# nf10_addon.net
KiCad netlist of a schematic drawn in Altium Designer
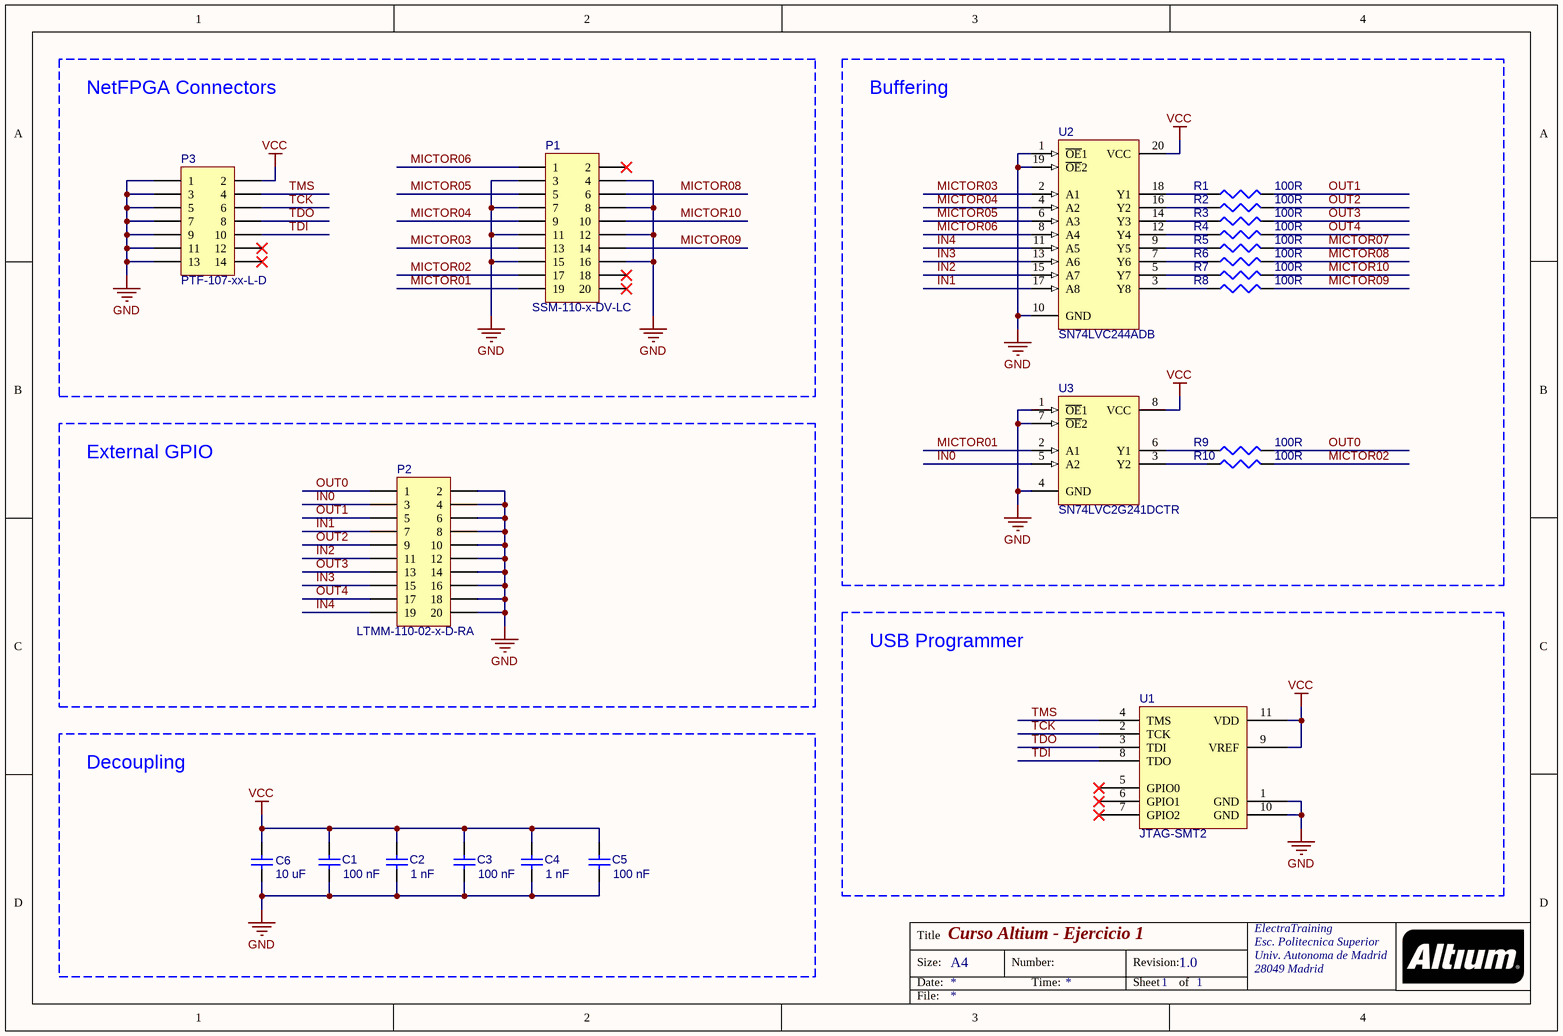
[diagram p0: nf10_addon.SchDoc]

(export (version "E")
  (design (tool "Eeschema 10.0.6"))
  (components
    (comp (ref "C1")
      (value "100 nF")
      (footprint "CAPC0603(1608)100_N")
      (description "Capacitor")
      (fields (field (name "Comment") "Cap") (field (name "PUBLISHER") "Altium Limited"))
      (libsource (lib "Miscellaneous Devices") (part "Cap"))
    )
    (comp (ref "C2")
      (value "1 nF")
      (footprint "CAPC0603(1608)100_N")
      (description "Capacitor")
      (fields (field (name "Comment") "Cap") (field (name "PUBLISHER") "Altium Limited"))
      (libsource (lib "Miscellaneous Devices") (part "Cap"))
    )
    (comp (ref "C3")
      (value "100 nF")
      (footprint "CAPC0603(1608)100_N")
      (description "Capacitor")
      (fields (field (name "Comment") "Cap") (field (name "PUBLISHER") "Altium Limited"))
      (libsource (lib "Miscellaneous Devices") (part "Cap"))
    )
    (comp (ref "C4")
      (value "1 nF")
      (footprint "CAPC0603(1608)100_N")
      (description "Capacitor")
      (fields (field (name "Comment") "Cap") (field (name "PUBLISHER") "Altium Limited"))
      (libsource (lib "Miscellaneous Devices") (part "Cap"))
    )
    (comp (ref "C5")
      (value "100 nF")
      (footprint "CAPC0603(1608)100_N")
      (description "Capacitor")
      (fields (field (name "Comment") "Cap") (field (name "PUBLISHER") "Altium Limited"))
      (libsource (lib "Miscellaneous Devices") (part "Cap"))
    )
    (comp (ref "C6")
      (value "10 uF")
      (footprint "CAPC1206(3216)100_N")
      (description "Capacitor")
      (fields (field (name "Comment") "Cap") (field (name "PUBLISHER") "Altium Limited"))
      (libsource (lib "Miscellaneous Devices") (part "Cap"))
    )
    (comp (ref "P1")
      (value "SSM-110-x-DV-LC")
      (footprint "SSM-110-X-DV-LC")
      (description "Samtec SSM-110-x-DV-LC")
      (fields (field (name "PUBLISHER") "Altium Limited"))
      (libsource (lib "nf10_addon") (part "SSM-110-x-DV-LC"))
    )
    (comp (ref "P2")
      (value "LTMM-110-02-x-D-RA")
      (footprint "LTMM-110-02-X-D-RA")
      (description "Samtec LTMM-110-02-x-D-RA")
      (fields (field (name "PUBLISHER") "Altium Limited"))
      (libsource (lib "nf10_addon") (part "LTMM-110-02-x-D-RA"))
    )
    (comp (ref "P3")
      (value "PTF-107-xx-L-D")
      (footprint "PTF-107-XX-L-D")
      (description "Samtec PTF-107-xx-L-D")
      (fields (field (name "PUBLISHER") "Altium Limited"))
      (libsource (lib "nf10_addon") (part "PTF-107-xx-L-D"))
    )
    (comp (ref "R1")
      (value "100R")
      (footprint "RESC0603(1608)_N")
      (description "Resistor")
      (fields (field (name "Comment") "Res3") (field (name "PUBLISHER") "Altium Limited"))
      (libsource (lib "Miscellaneous Devices") (part "Res3"))
    )
    (comp (ref "R2")
      (value "100R")
      (footprint "RESC0603(1608)_N")
      (description "Resistor")
      (fields (field (name "Comment") "Res3") (field (name "PUBLISHER") "Altium Limited"))
      (libsource (lib "Miscellaneous Devices") (part "Res3"))
    )
    (comp (ref "R3")
      (value "100R")
      (footprint "RESC0603(1608)_N")
      (description "Resistor")
      (fields (field (name "Comment") "Res3") (field (name "PUBLISHER") "Altium Limited"))
      (libsource (lib "Miscellaneous Devices") (part "Res3"))
    )
    (comp (ref "R4")
      (value "100R")
      (footprint "RESC0603(1608)_N")
      (description "Resistor")
      (fields (field (name "Comment") "Res3") (field (name "PUBLISHER") "Altium Limited"))
      (libsource (lib "Miscellaneous Devices") (part "Res3"))
    )
    (comp (ref "R5")
      (value "100R")
      (footprint "RESC0603(1608)_N")
      (description "Resistor")
      (fields (field (name "Comment") "Res3") (field (name "PUBLISHER") "Altium Limited"))
      (libsource (lib "Miscellaneous Devices") (part "Res3"))
    )
    (comp (ref "R6")
      (value "100R")
      (footprint "RESC0603(1608)_N")
      (description "Resistor")
      (fields (field (name "Comment") "Res3") (field (name "PUBLISHER") "Altium Limited"))
      (libsource (lib "Miscellaneous Devices") (part "Res3"))
    )
    (comp (ref "R7")
      (value "100R")
      (footprint "RESC0603(1608)_N")
      (description "Resistor")
      (fields (field (name "Comment") "Res3") (field (name "PUBLISHER") "Altium Limited"))
      (libsource (lib "Miscellaneous Devices") (part "Res3"))
    )
    (comp (ref "R8")
      (value "100R")
      (footprint "RESC0603(1608)_N")
      (description "Resistor")
      (fields (field (name "Comment") "Res3") (field (name "PUBLISHER") "Altium Limited"))
      (libsource (lib "Miscellaneous Devices") (part "Res3"))
    )
    (comp (ref "R9")
      (value "100R")
      (footprint "RESC0603(1608)_N")
      (description "Resistor")
      (fields (field (name "Comment") "Res3") (field (name "PUBLISHER") "Altium Limited"))
      (libsource (lib "Miscellaneous Devices") (part "Res3"))
    )
    (comp (ref "R10")
      (value "100R")
      (footprint "RESC0603(1608)_N")
      (description "Resistor")
      (fields (field (name "Comment") "Res3") (field (name "PUBLISHER") "Altium Limited"))
      (libsource (lib "Miscellaneous Devices") (part "Res3"))
    )
    (comp (ref "U1")
      (value "JTAG-SMT2")
      (footprint "JTAG-SMT2")
      (libsource (lib "NetFPGA10G_Addon") (part "JTAG_SMT2"))
    )
    (comp (ref "U2")
      (value "SN74LVC244ADB")
      (footprint "DB020_N")
      (description "Octal Buffer/Driver with 3-State Outputs")
      (fields (field (name "PUBLISHER") "Altium Limited"))
      (libsource (lib "TI Logic Buffer Line Driver") (part "SN74LVC244ADB"))
    )
    (comp (ref "U3")
      (value "SN74LVC2G241DCTR")
      (footprint "DCT08_N")
      (description "Quadruple Bus Buffer Gate with 3- State Outputs")
      (fields (field (name "PUBLISHER") "Altium Limited"))
      (libsource (lib "nf10_addon") (part "SN74LVC2G241DCTR"))
    )
  )
  (nets
    (net (code "1") (name "/IN0") (class "Default")
      (node (ref "P2") (pin "3") (pinfunction "3_3") (pintype "passive"))
      (node (ref "U3") (pin "5") (pinfunction "A2_5") (pintype "input"))
    )
    (net (code "2") (name "/IN1") (class "Default")
      (node (ref "P2") (pin "7") (pinfunction "7_7") (pintype "passive"))
      (node (ref "U2") (pin "17") (pinfunction "A8_17") (pintype "input"))
    )
    (net (code "3") (name "/IN2") (class "Default")
      (node (ref "P2") (pin "11") (pinfunction "11_11") (pintype "passive"))
      (node (ref "U2") (pin "15") (pinfunction "A7_15") (pintype "input"))
    )
    (net (code "4") (name "/IN3") (class "Default")
      (node (ref "P2") (pin "15") (pinfunction "15_15") (pintype "passive"))
      (node (ref "U2") (pin "13") (pinfunction "A6_13") (pintype "input"))
    )
    (net (code "5") (name "/IN4") (class "Default")
      (node (ref "P2") (pin "19") (pinfunction "19_19") (pintype "passive"))
      (node (ref "U2") (pin "11") (pinfunction "A5_11") (pintype "input"))
    )
    (net (code "6") (name "/MICTOR01") (class "Default")
      (node (ref "P1") (pin "19") (pinfunction "19_19") (pintype "passive"))
      (node (ref "U3") (pin "2") (pinfunction "A1_2") (pintype "input"))
    )
    (net (code "7") (name "/MICTOR02") (class "Default")
      (node (ref "P1") (pin "17") (pinfunction "17_17") (pintype "passive"))
      (node (ref "R10") (pin "2") (pinfunction "2_2") (pintype "passive"))
    )
    (net (code "8") (name "/MICTOR03") (class "Default")
      (node (ref "P1") (pin "13") (pinfunction "13_13") (pintype "passive"))
      (node (ref "U2") (pin "2") (pinfunction "A1_2") (pintype "input"))
    )
    (net (code "9") (name "/MICTOR04") (class "Default")
      (node (ref "P1") (pin "9") (pinfunction "9_9") (pintype "passive"))
      (node (ref "U2") (pin "4") (pinfunction "A2_4") (pintype "input"))
    )
    (net (code "10") (name "/MICTOR05") (class "Default")
      (node (ref "P1") (pin "5") (pinfunction "5_5") (pintype "passive"))
      (node (ref "U2") (pin "6") (pinfunction "A3_6") (pintype "input"))
    )
    (net (code "11") (name "/MICTOR06") (class "Default")
      (node (ref "P1") (pin "1") (pinfunction "1_1") (pintype "passive"))
      (node (ref "U2") (pin "8") (pinfunction "A4_8") (pintype "input"))
    )
    (net (code "12") (name "/MICTOR07") (class "Default")
      (node (ref "R5") (pin "2") (pinfunction "2_2") (pintype "passive"))
    )
    (net (code "13") (name "/MICTOR08") (class "Default")
      (node (ref "P1") (pin "6") (pinfunction "6_6") (pintype "passive"))
      (node (ref "R6") (pin "2") (pinfunction "2_2") (pintype "passive"))
    )
    (net (code "14") (name "/MICTOR09") (class "Default")
      (node (ref "P1") (pin "14") (pinfunction "14_14") (pintype "passive"))
      (node (ref "R8") (pin "2") (pinfunction "2_2") (pintype "passive"))
    )
    (net (code "15") (name "/MICTOR10") (class "Default")
      (node (ref "P1") (pin "10") (pinfunction "10_10") (pintype "passive"))
      (node (ref "R7") (pin "2") (pinfunction "2_2") (pintype "passive"))
    )
    (net (code "16") (name "/OUT0") (class "Default")
      (node (ref "P2") (pin "1") (pinfunction "1_1") (pintype "passive"))
      (node (ref "R9") (pin "2") (pinfunction "2_2") (pintype "passive"))
    )
    (net (code "17") (name "/OUT1") (class "Default")
      (node (ref "P2") (pin "5") (pinfunction "5_5") (pintype "passive"))
      (node (ref "R1") (pin "2") (pinfunction "2_2") (pintype "passive"))
    )
    (net (code "18") (name "/OUT2") (class "Default")
      (node (ref "P2") (pin "9") (pinfunction "9_9") (pintype "passive"))
      (node (ref "R2") (pin "2") (pinfunction "2_2") (pintype "passive"))
    )
    (net (code "19") (name "/OUT3") (class "Default")
      (node (ref "P2") (pin "13") (pinfunction "13_13") (pintype "passive"))
      (node (ref "R3") (pin "2") (pinfunction "2_2") (pintype "passive"))
    )
    (net (code "20") (name "/OUT4") (class "Default")
      (node (ref "P2") (pin "17") (pinfunction "17_17") (pintype "passive"))
      (node (ref "R4") (pin "2") (pinfunction "2_2") (pintype "passive"))
    )
    (net (code "21") (name "/TCK") (class "Default")
      (node (ref "P3") (pin "6") (pinfunction "6_6") (pintype "passive"))
      (node (ref "U1") (pin "2") (pinfunction "TCK_2") (pintype "passive"))
    )
    (net (code "22") (name "/TDI") (class "Default")
      (node (ref "P3") (pin "10") (pinfunction "10_10") (pintype "passive"))
      (node (ref "U1") (pin "8") (pinfunction "TDO_8") (pintype "passive"))
    )
    (net (code "23") (name "/TDO") (class "Default")
      (node (ref "P3") (pin "8") (pinfunction "8_8") (pintype "passive"))
      (node (ref "U1") (pin "3") (pinfunction "TDI_3") (pintype "passive"))
    )
    (net (code "24") (name "/TMS") (class "Default")
      (node (ref "P3") (pin "4") (pinfunction "4_4") (pintype "passive"))
      (node (ref "U1") (pin "4") (pinfunction "TMS_4") (pintype "passive"))
    )
    (net (code "25") (name "GND") (class "Default")
      (node (ref "C1") (pin "1") (pinfunction "1_1") (pintype "passive"))
      (node (ref "C2") (pin "1") (pinfunction "1_1") (pintype "passive"))
      (node (ref "C3") (pin "1") (pinfunction "1_1") (pintype "passive"))
      (node (ref "C4") (pin "1") (pinfunction "1_1") (pintype "passive"))
      (node (ref "C5") (pin "1") (pinfunction "1_1") (pintype "passive"))
      (node (ref "C6") (pin "1") (pinfunction "1_1") (pintype "passive"))
      (node (ref "P1") (pin "11") (pinfunction "11_11") (pintype "passive"))
      (node (ref "P1") (pin "12") (pinfunction "12_12") (pintype "passive"))
      (node (ref "P1") (pin "15") (pinfunction "15_15") (pintype "passive"))
      (node (ref "P1") (pin "16") (pinfunction "16_16") (pintype "passive"))
      (node (ref "P1") (pin "3") (pinfunction "3_3") (pintype "passive"))
      (node (ref "P1") (pin "4") (pinfunction "4_4") (pintype "passive"))
      (node (ref "P1") (pin "7") (pinfunction "7_7") (pintype "passive"))
      (node (ref "P1") (pin "8") (pinfunction "8_8") (pintype "passive"))
      (node (ref "P2") (pin "10") (pinfunction "10_10") (pintype "passive"))
      (node (ref "P2") (pin "12") (pinfunction "12_12") (pintype "passive"))
      (node (ref "P2") (pin "14") (pinfunction "14_14") (pintype "passive"))
      (node (ref "P2") (pin "16") (pinfunction "16_16") (pintype "passive"))
      (node (ref "P2") (pin "18") (pinfunction "18_18") (pintype "passive"))
      (node (ref "P2") (pin "2") (pinfunction "2_2") (pintype "passive"))
      (node (ref "P2") (pin "20") (pinfunction "20_20") (pintype "passive"))
      (node (ref "P2") (pin "4") (pinfunction "4_4") (pintype "passive"))
      (node (ref "P2") (pin "6") (pinfunction "6_6") (pintype "passive"))
      (node (ref "P2") (pin "8") (pinfunction "8_8") (pintype "passive"))
      (node (ref "P3") (pin "1") (pinfunction "1_1") (pintype "passive"))
      (node (ref "P3") (pin "11") (pinfunction "11_11") (pintype "passive"))
      (node (ref "P3") (pin "13") (pinfunction "13_13") (pintype "passive"))
      (node (ref "P3") (pin "3") (pinfunction "3_3") (pintype "passive"))
      (node (ref "P3") (pin "5") (pinfunction "5_5") (pintype "passive"))
      (node (ref "P3") (pin "7") (pinfunction "7_7") (pintype "passive"))
      (node (ref "P3") (pin "9") (pinfunction "9_9") (pintype "passive"))
      (node (ref "U1") (pin "1") (pinfunction "GND_1") (pintype "passive"))
      (node (ref "U1") (pin "10") (pinfunction "GND_10") (pintype "passive"))
      (node (ref "U2") (pin "1") (pinfunction "~{OE}1_1") (pintype "input"))
      (node (ref "U2") (pin "10") (pinfunction "GND_10") (pintype "power_in"))
      (node (ref "U2") (pin "19") (pinfunction "~{OE}2_19") (pintype "input"))
      (node (ref "U3") (pin "1") (pinfunction "~{OE}1_1") (pintype "input"))
      (node (ref "U3") (pin "4") (pinfunction "GND_4") (pintype "power_in"))
      (node (ref "U3") (pin "7") (pinfunction "~{OE}2_7") (pintype "input"))
    )
    (net (code "26") (name "Net-(U2-Y1)") (class "Default")
      (node (ref "R1") (pin "1") (pinfunction "1_1") (pintype "passive"))
      (node (ref "U2") (pin "18") (pinfunction "Y1_18") (pintype "tri_state"))
    )
    (net (code "27") (name "Net-(U2-Y2)") (class "Default")
      (node (ref "R2") (pin "1") (pinfunction "1_1") (pintype "passive"))
      (node (ref "U2") (pin "16") (pinfunction "Y2_16") (pintype "tri_state"))
    )
    (net (code "28") (name "Net-(U2-Y3)") (class "Default")
      (node (ref "R3") (pin "1") (pinfunction "1_1") (pintype "passive"))
      (node (ref "U2") (pin "14") (pinfunction "Y3_14") (pintype "tri_state"))
    )
    (net (code "29") (name "Net-(U2-Y4)") (class "Default")
      (node (ref "R4") (pin "1") (pinfunction "1_1") (pintype "passive"))
      (node (ref "U2") (pin "12") (pinfunction "Y4_12") (pintype "tri_state"))
    )
    (net (code "30") (name "Net-(U2-Y5)") (class "Default")
      (node (ref "R5") (pin "1") (pinfunction "1_1") (pintype "passive"))
      (node (ref "U2") (pin "9") (pinfunction "Y5_9") (pintype "tri_state"))
    )
    (net (code "31") (name "Net-(U2-Y6)") (class "Default")
      (node (ref "R6") (pin "1") (pinfunction "1_1") (pintype "passive"))
      (node (ref "U2") (pin "7") (pinfunction "Y6_7") (pintype "tri_state"))
    )
    (net (code "32") (name "Net-(U2-Y7)") (class "Default")
      (node (ref "R7") (pin "1") (pinfunction "1_1") (pintype "passive"))
      (node (ref "U2") (pin "5") (pinfunction "Y7_5") (pintype "tri_state"))
    )
    (net (code "33") (name "Net-(U2-Y8)") (class "Default")
      (node (ref "R8") (pin "1") (pinfunction "1_1") (pintype "passive"))
      (node (ref "U2") (pin "3") (pinfunction "Y8_3") (pintype "tri_state"))
    )
    (net (code "34") (name "Net-(U3-Y1)") (class "Default")
      (node (ref "R9") (pin "1") (pinfunction "1_1") (pintype "passive"))
      (node (ref "U3") (pin "6") (pinfunction "Y1_6") (pintype "tri_state"))
    )
    (net (code "35") (name "Net-(U3-Y2)") (class "Default")
      (node (ref "R10") (pin "1") (pinfunction "1_1") (pintype "passive"))
      (node (ref "U3") (pin "3") (pinfunction "Y2_3") (pintype "tri_state"))
    )
    (net (code "36") (name "VCC") (class "Default")
      (node (ref "C1") (pin "2") (pinfunction "2_2") (pintype "passive"))
      (node (ref "C2") (pin "2") (pinfunction "2_2") (pintype "passive"))
      (node (ref "C3") (pin "2") (pinfunction "2_2") (pintype "passive"))
      (node (ref "C4") (pin "2") (pinfunction "2_2") (pintype "passive"))
      (node (ref "C5") (pin "2") (pinfunction "2_2") (pintype "passive"))
      (node (ref "C6") (pin "2") (pinfunction "2_2") (pintype "passive"))
      (node (ref "P3") (pin "2") (pinfunction "2_2") (pintype "passive"))
      (node (ref "U1") (pin "11") (pinfunction "VDD_11") (pintype "passive"))
      (node (ref "U1") (pin "9") (pinfunction "VREF_9") (pintype "passive"))
      (node (ref "U2") (pin "20") (pinfunction "VCC_20") (pintype "power_in"))
      (node (ref "U3") (pin "8") (pinfunction "VCC_8") (pintype "power_in"))
    )
    (net (code "37") (name "unconnected-(P1-Pad2)") (class "Default")
      (node (ref "P1") (pin "2") (pinfunction "2_2") (pintype "passive+no_connect"))
    )
    (net (code "38") (name "unconnected-(P1-Pad18)") (class "Default")
      (node (ref "P1") (pin "18") (pinfunction "18_18") (pintype "passive+no_connect"))
    )
    (net (code "39") (name "unconnected-(P1-Pad20)") (class "Default")
      (node (ref "P1") (pin "20") (pinfunction "20_20") (pintype "passive+no_connect"))
    )
    (net (code "40") (name "unconnected-(P3-Pad12)") (class "Default")
      (node (ref "P3") (pin "12") (pinfunction "12_12") (pintype "passive+no_connect"))
    )
    (net (code "41") (name "unconnected-(P3-Pad14)") (class "Default")
      (node (ref "P3") (pin "14") (pinfunction "14_14") (pintype "passive+no_connect"))
    )
    (net (code "42") (name "unconnected-(U1-GPIO0-Pad5)") (class "Default")
      (node (ref "U1") (pin "5") (pinfunction "GPIO0_5") (pintype "passive+no_connect"))
    )
    (net (code "43") (name "unconnected-(U1-GPIO1-Pad6)") (class "Default")
      (node (ref "U1") (pin "6") (pinfunction "GPIO1_6") (pintype "passive+no_connect"))
    )
    (net (code "44") (name "unconnected-(U1-GPIO2-Pad7)") (class "Default")
      (node (ref "U1") (pin "7") (pinfunction "GPIO2_7") (pintype "passive+no_connect"))
    )
  )
)
